# Probe.net
KiCad netlist of a schematic drawn in Altium Designer
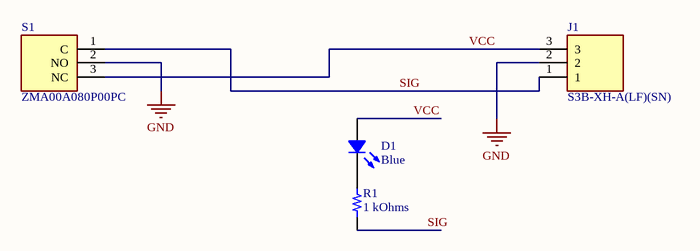
[diagram p0: Probe.SchDoc]

(export (version "E")
  (design (tool "Eeschema 10.0.6"))
  (components
    (comp (ref "D1")
      (value "Blue")
      (footprint "LED 0805_2012 BLUE")
      (description "LED BLUE 0805 SMD")
      (fields (field (name "PART NUMBER") "5990191007F") (field (name "MANUFACTURER") "Dialight"))
      (libsource (lib "Celestial Altium Library - altium_library") (part "LED"))
    )
    (comp (ref "J1")
      (value "S3B-XH-A(LF)(SN)")
      (footprint "S3B-XH-A(LF)(SN):JST_S3B-XH-A(LF)(SN)")
      (description "Connector Header Through Hole, Right Angle 3 position 0.098\" (2.50mm)")
      (fields (field (name "MF") "{'manufacturer': u'JST Sales America Inc.'}"))
      (libsource (lib "S3B-XH-A(LF)(SN)") (part "S3B-XH-A(LF)(SN)"))
    )
    (comp (ref "R1")
      (value "1 kOhms")
      (footprint "RES 0805_2012")
      (description "RES 1K OHM 1% 1/4W 0805")
      (fields
        (field (name "PART NUMBER") "RNCP0805FTD1K00")
        (field (name "MANUFACTURER") "Stackpole Electronics Inc")
      )
      (libsource (lib "Celestial Altium Library - altium_library") (part "Resistor"))
    )
    (comp (ref "S1")
      (value "ZMA00A080P00PC")
      (footprint "SamacSys:ZMA00A080P00PC")
      (description "Switch")
      (libsource (lib "SamacSys") (part "ZMA00A080P00PC"))
    )
  )
  (nets
    (net (code "1") (name "/SIG") (class "Default")
      (node (ref "J1") (pin "1") (pinfunction "1_1") (pintype "passive"))
      (node (ref "R1") (pin "1") (pinfunction "1_1") (pintype "passive"))
      (node (ref "S1") (pin "1") (pinfunction "C_1") (pintype "passive"))
    )
    (net (code "2") (name "/VCC") (class "Default")
      (node (ref "D1") (pin "1") (pinfunction "1_1") (pintype "passive"))
      (node (ref "J1") (pin "3") (pinfunction "3_3") (pintype "passive"))
      (node (ref "S1") (pin "3") (pinfunction "NC_3") (pintype "passive"))
    )
    (net (code "3") (name "GND") (class "Default")
      (node (ref "J1") (pin "2") (pinfunction "2_2") (pintype "passive"))
      (node (ref "S1") (pin "2") (pinfunction "NO_2") (pintype "passive"))
    )
    (net (code "4") (name "Net-(D1-Pad2)") (class "Default")
      (node (ref "D1") (pin "2") (pinfunction "2_2") (pintype "passive"))
      (node (ref "R1") (pin "2") (pinfunction "2_2") (pintype "passive"))
    )
  )
)
